# H1AR30.net
KiCad netlist of a schematic drawn in EAGLE
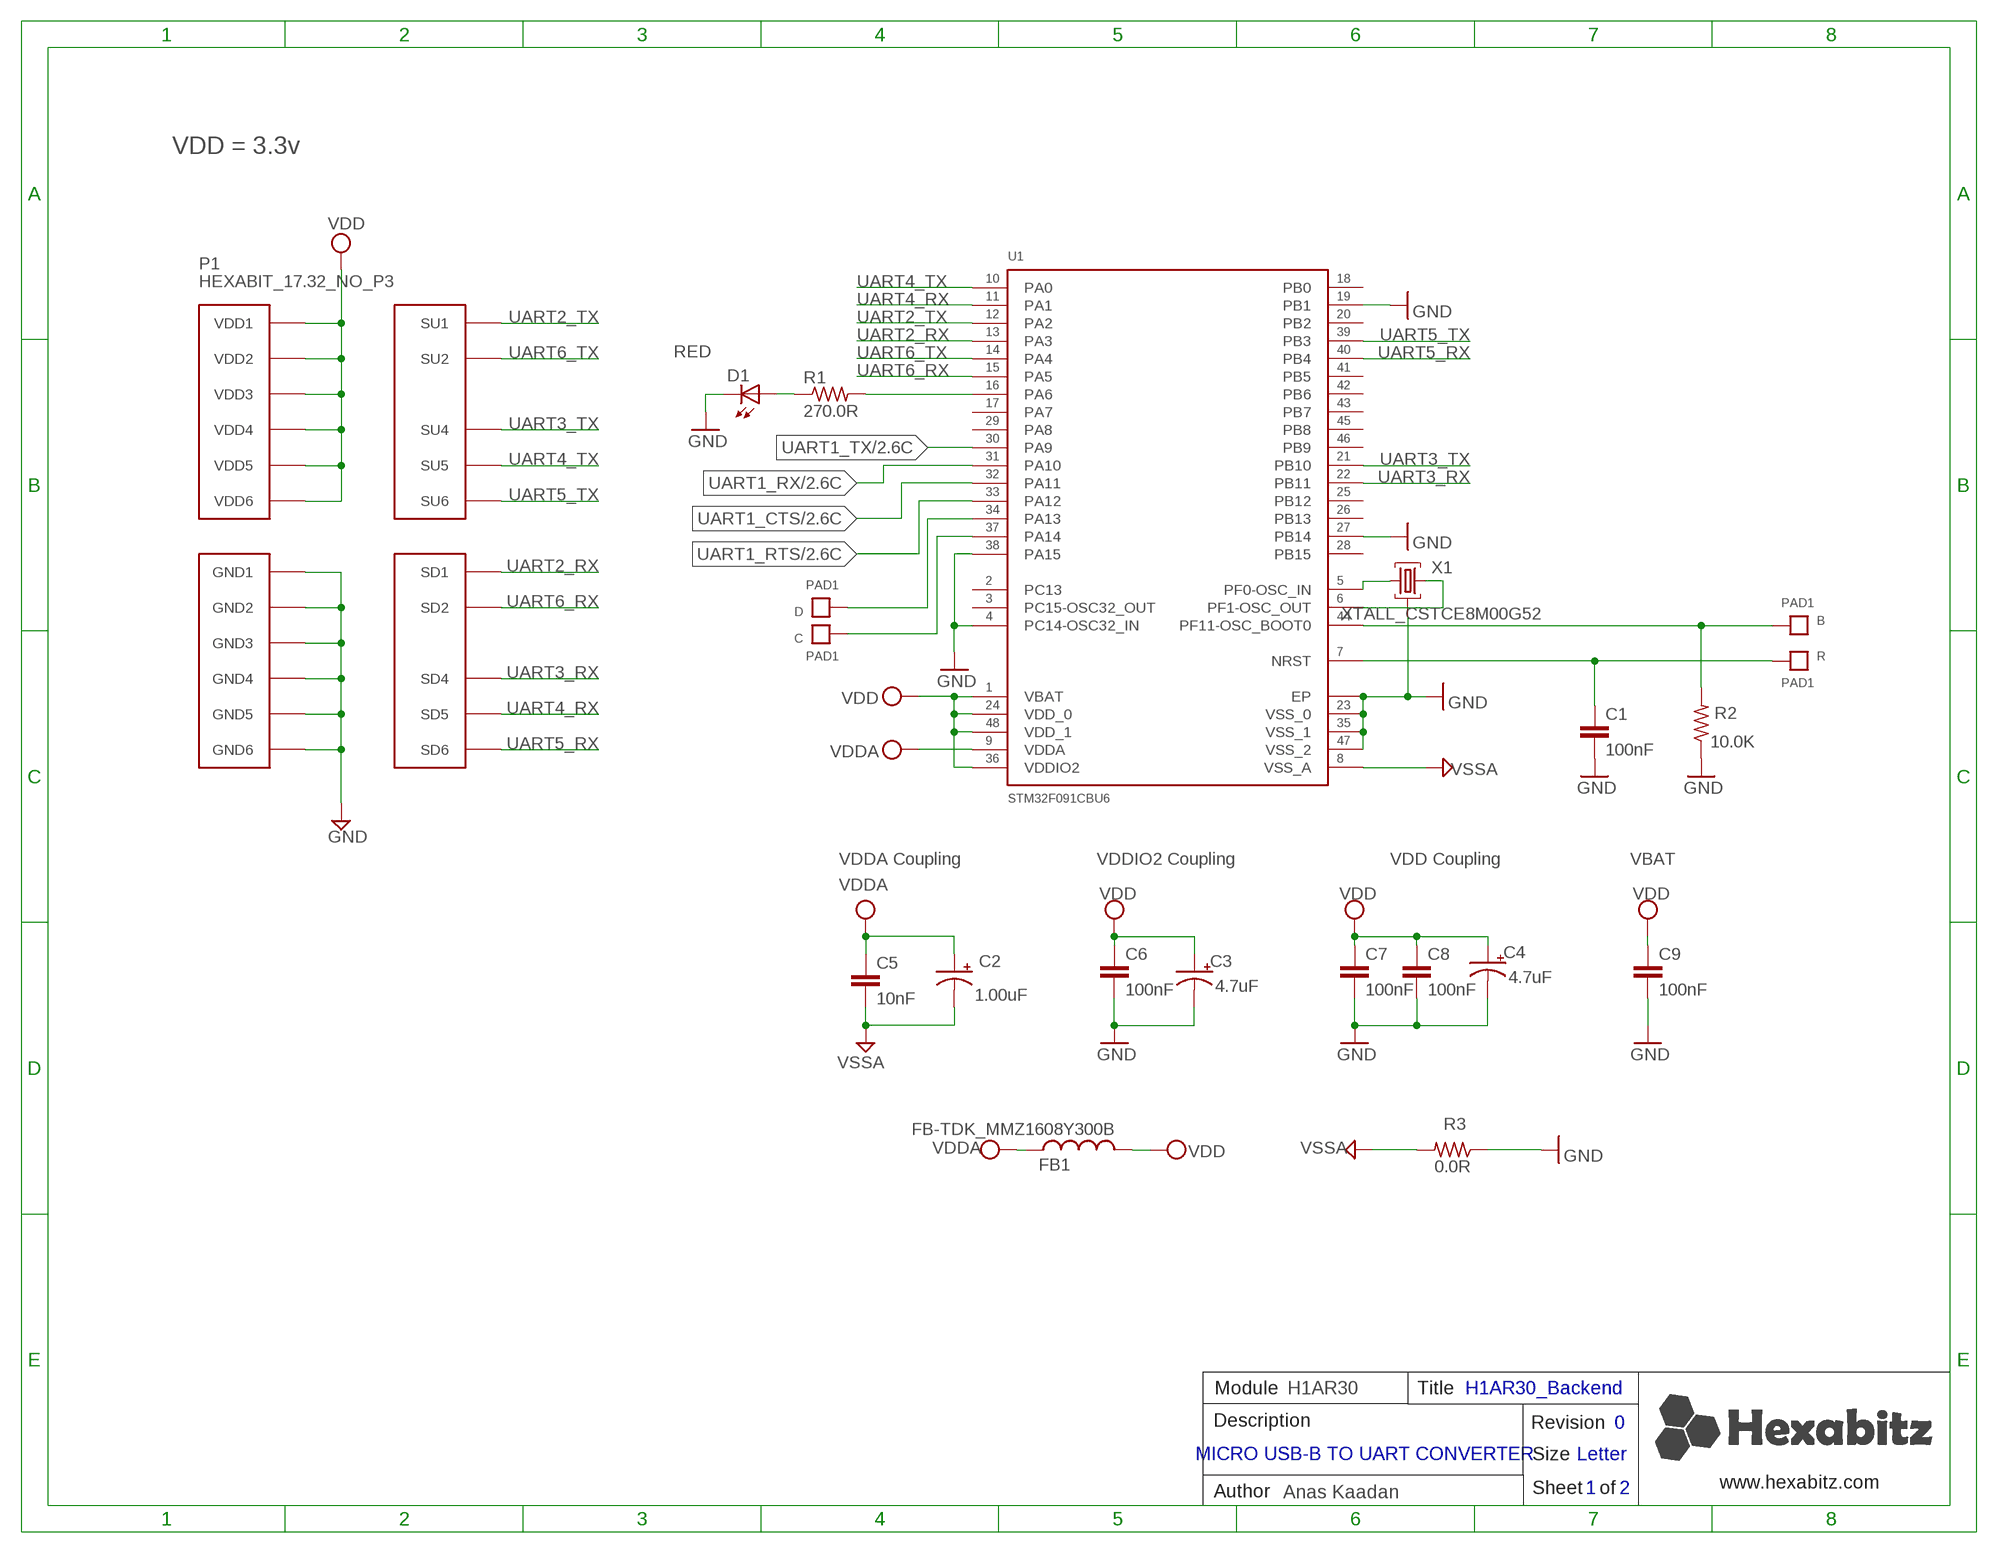
[diagram p0: schematic, sheet 1]
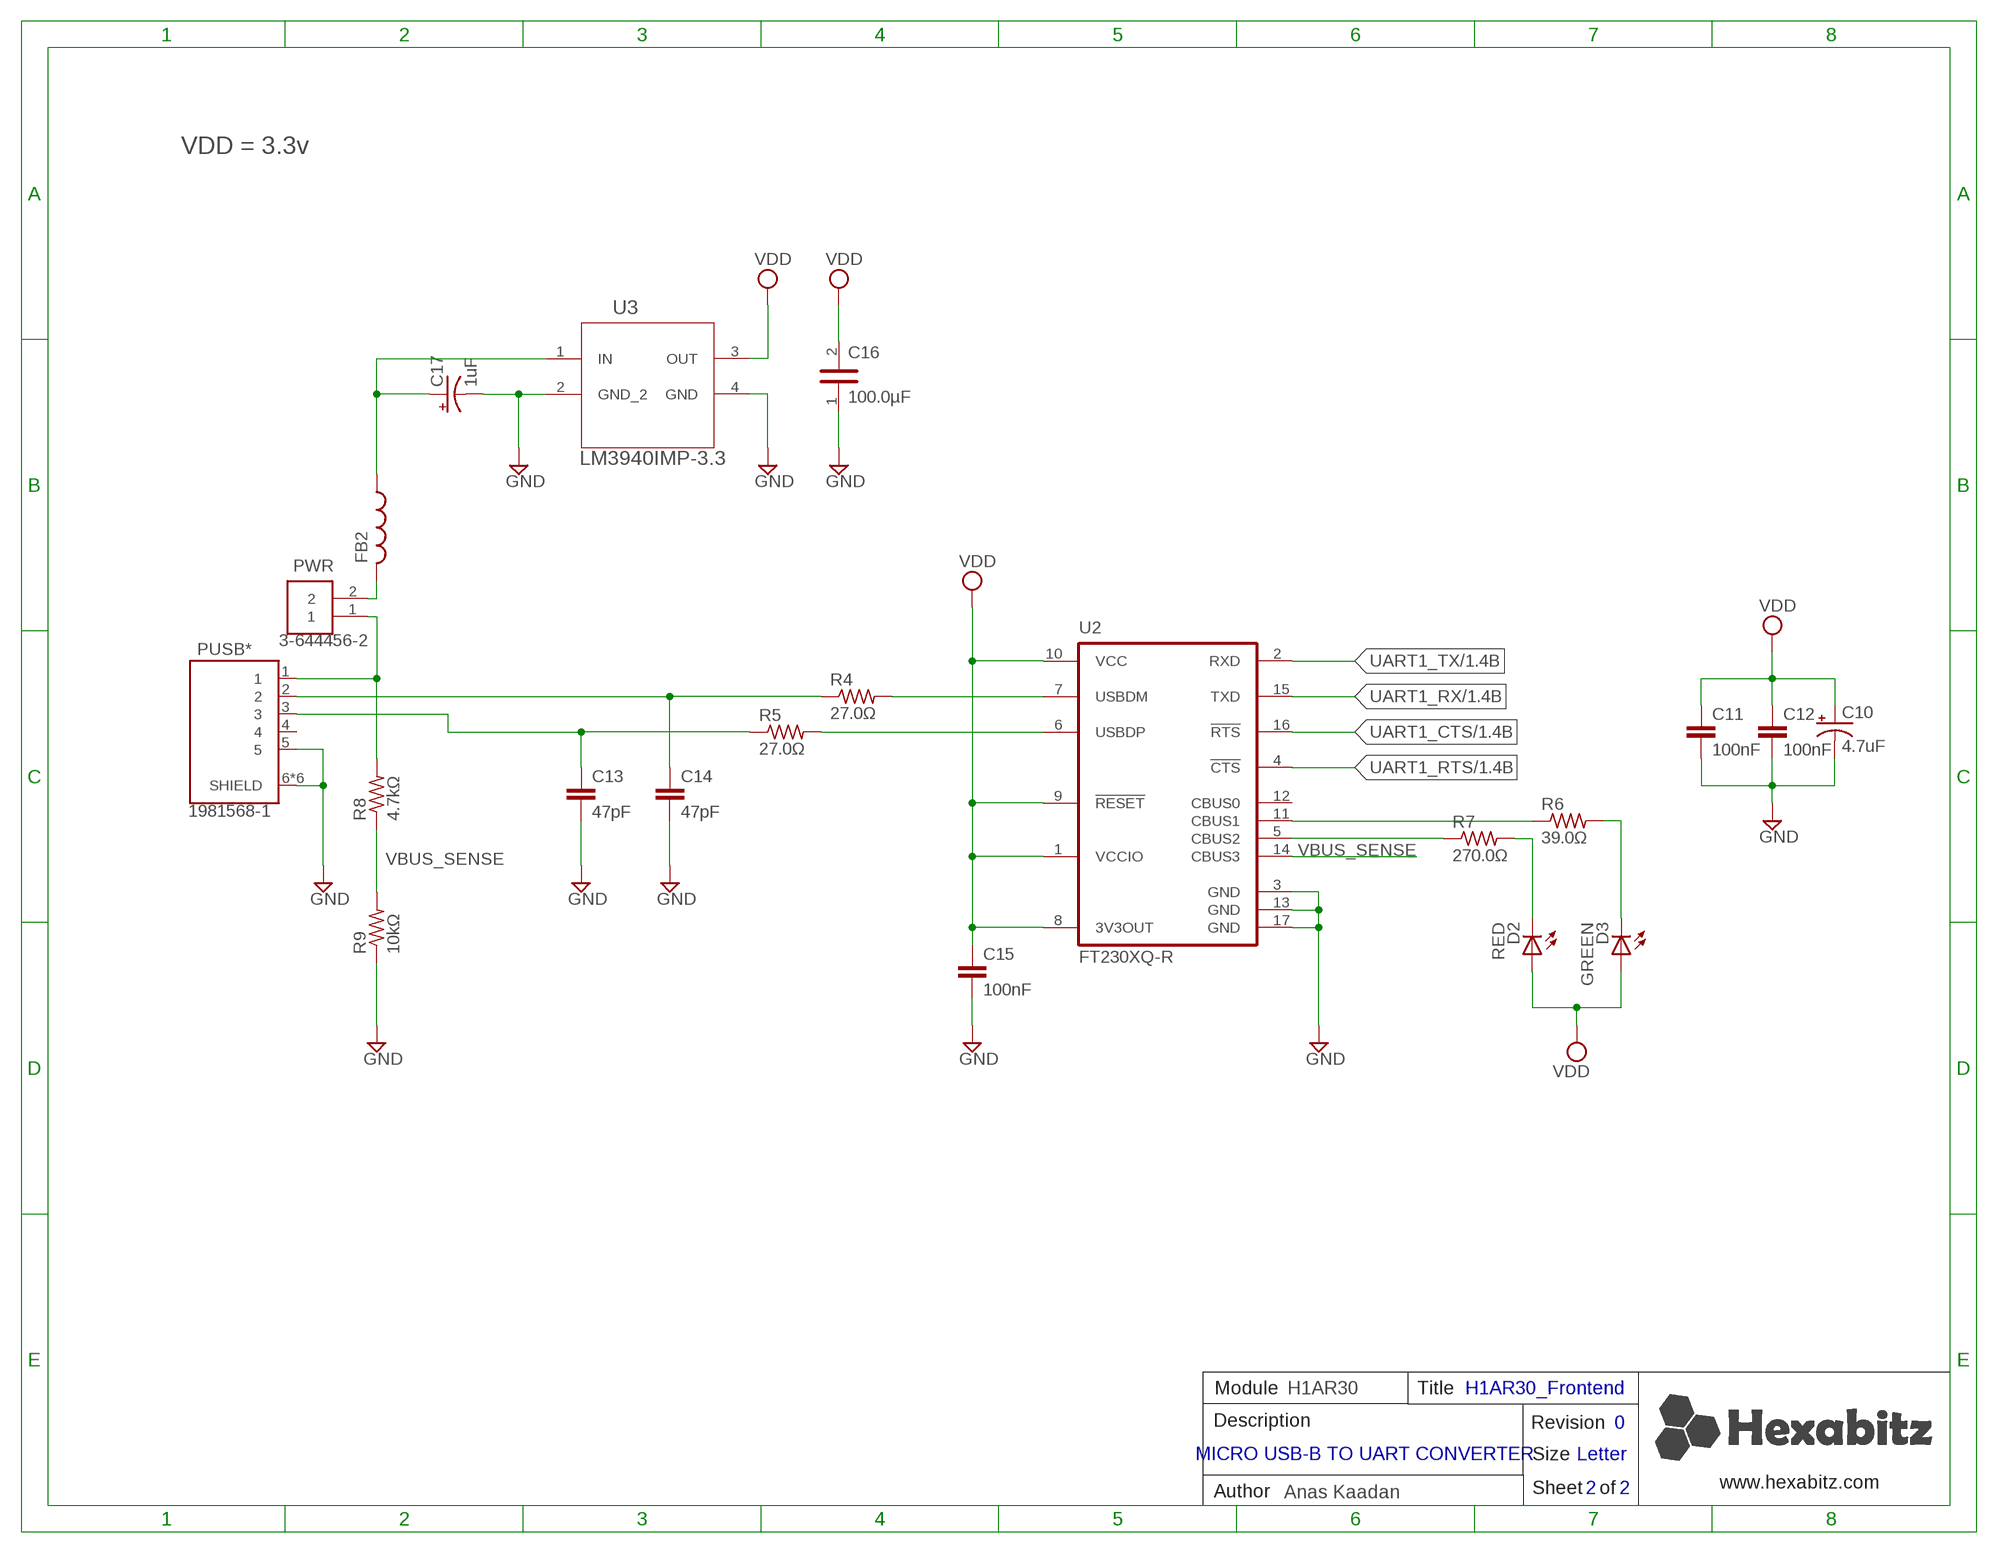
[diagram p1: schematic, sheet 2]

(export (version "E")
  (design (tool "Eeschema 10.0.6"))
  (components
    (comp (ref "C10")
      (value "4.7uF")
      (footprint "eagle-import:C-0805-POL")
      (fields
        (field (name "CAPACITANCE") "4.7 µF")
        (field (name "MFN") "Panasonic")
        (field (name "MPN") "10TPU4R7MSI")
        (field (name "OCTOPART_URL") "https://octopart.com/10tpu4r7msi-panasonic-29487748")
        (field (name "TOLERANCE") "±20%")
        (field (name "VOLTAGE_RATING") "10.0 V")
      )
      (libsource (lib "eagle-import") (part "C-0805-POL"))
    )
    (comp (ref "C11")
      (value "100nF")
      (footprint "eagle-import:C-0603")
      (fields
        (field (name "CAPACITANCE") "100 nF")
        (field (name "MFN") "AVX")
        (field (name "MPN") "0603YC104K4T2A")
        (field (name "OCTOPART_URL") "https://octopart.com/0603yc104k4t2a-avx+interconnect+%2F+elco-8120651")
        (field (name "TOLERANCE") "±10%")
        (field (name "VOLTAGE_RATING") "16.0 V")
      )
      (libsource (lib "eagle-import") (part "C-0603"))
    )
    (comp (ref "C12")
      (value "100nF")
      (footprint "eagle-import:C-0603")
      (fields
        (field (name "CAPACITANCE") "100 nF")
        (field (name "MFN") "AVX")
        (field (name "MPN") "0603YC104K4T2A")
        (field (name "OCTOPART_URL") "https://octopart.com/0603yc104k4t2a-avx+interconnect+%2F+elco-8120651")
        (field (name "TOLERANCE") "±10%")
        (field (name "VOLTAGE_RATING") "16.0 V")
      )
      (libsource (lib "eagle-import") (part "C-0603"))
    )
    (comp (ref "C13")
      (value "47pF")
      (footprint "eagle-import:C-0603")
      (fields
        (field (name "CAPACITANCE") "47 pF")
        (field (name "MFN") "AVX")
        (field (name "MPN") "06035A470JAT2A")
        (field (name "OCTOPART_URL") "https://octopart.com/c3225x5r0j107m250ac-tdk-25947844?r=spc#")
        (field (name "TOLERANCE") "±5%")
        (field (name "VOLTAGE_RATING") "50.0 V")
      )
      (libsource (lib "eagle-import") (part "C-0603"))
    )
    (comp (ref "C14")
      (value "47pF")
      (footprint "eagle-import:C-0603")
      (fields
        (field (name "CAPACITANCE") "47 pF")
        (field (name "MFN") "AVX")
        (field (name "MPN") "06035A470JAT2A")
        (field (name "OCTOPART_URL") "https://octopart.com/06035a470jat2a-avx+interconnect+%2F+elco-46507018")
        (field (name "TOLERANCE") "±5%")
        (field (name "VOLTAGE_RATING") "50.0 V")
      )
      (libsource (lib "eagle-import") (part "C-0603"))
    )
    (comp (ref "C15")
      (value "100nF")
      (footprint "eagle-import:C-0603")
      (fields
        (field (name "CAPACITANCE") "100 nF")
        (field (name "MFN") "AVX")
        (field (name "MPN") "0603YC104K4T2A")
        (field (name "OCTOPART_URL") "https://octopart.com/0603yc104k4t2a-avx+interconnect+%2F+elco-8120651")
        (field (name "TOLERANCE") "±10%")
        (field (name "VOLTAGE_RATING") "16.0 V")
      )
      (libsource (lib "eagle-import") (part "C-0603"))
    )
    (comp (ref "C16")
      (value "100uF")
      (footprint "eagle-import:C-3225")
      (fields
        (field (name "CAPACITANCE") "100.0µF")
        (field (name "MPN") "C3225X5R0J107M250AC")
        (field (name "VOLTAGE") "6.3V")
      )
      (libsource (lib "eagle-import") (part "C-3225TDK_C3225X5R0J107M250AC_0_0"))
    )
    (comp (ref "C17")
      (value "1uF")
      (footprint "eagle-import:C-0805-POL")
      (fields
        (field (name "CAPACITANCE") "1.00 µF")
        (field (name "MFN") "AVX")
        (field (name "MPN") "TAJR105M016RNJ")
        (field (name "OCTOPART_URL") "http://octopart.com/tajr105m016rnj-avx-1188552")
        (field (name "TOLERANCE") "±20%")
        (field (name "VOLTAGE_RATING") "16.0 V")
      )
      (libsource (lib "eagle-import") (part "C-0805-POL"))
    )
    (comp (ref "D2")
      (value "RED")
      (footprint "eagle-import:VLMS1300-GS08")
      (fields (field (name "MPN") "VLMS1300-GS08"))
      (libsource (lib "eagle-import") (part "VLMS1300-GS08"))
    )
    (comp (ref "D3")
      (value "GREEN")
      (footprint "eagle-import:VLMS1300-GS08")
      (fields (field (name "MPN") "VLMTG1300-GS08"))
      (libsource (lib "eagle-import") (part "VLMTG1300-GS08"))
    )
    (comp (ref "FB2")
      (value "FB-TDK_MMZ1608Y300B")
      (footprint "eagle-import:FB-TDK_MMZ1608Y300B")
      (fields
        (field (name "MFN") "TDK")
        (field (name "MPN") "MMZ1608Y300B")
        (field (name "OCTOPART_URL") "https://octopart.com/mmz1608y300b-tdk-368280")
      )
      (libsource (lib "eagle-import") (part "FB-TDK_MMZ1608Y300B"))
    )
    (comp (ref "PUSB*")
      (value "1981568-1")
      (footprint "eagle-import:TE_1981568-1")
      (fields (field (name "MPN") "19815681"))
      (libsource (lib "eagle-import") (part "1981568-1"))
    )
    (comp (ref "PWR")
      (value "3-644456-2")
      (footprint "eagle-import:TE_3-644456-2")
      (fields (field (name "MF") "TE Connectivity"))
      (libsource (lib "eagle-import") (part "3-644456-2"))
    )
    (comp (ref "R4")
      (value "27.0Ω")
      (footprint "eagle-import:R-0603")
      (fields
        (field (name "MFN") "Vishay")
        (field (name "MPN") "CRCW060327R0FKEA")
        (field (name "OCTOPART_URL") "https://octopart.com/crcw060327r0fkea-vishay-39833156")
        (field (name "RESISTANCE") "27.0 Ω")
        (field (name "TOLERANCE") "±1%")
      )
      (libsource (lib "eagle-import") (part "R-0603"))
    )
    (comp (ref "R5")
      (value "27.0Ω")
      (footprint "eagle-import:R-0603")
      (fields
        (field (name "MFN") "Vishay")
        (field (name "MPN") "CRCW060327R0FKEA")
        (field (name "OCTOPART_URL") "https://octopart.com/crcw060327r0fkea-vishay-39833156")
        (field (name "RESISTANCE") "27.0 Ω")
        (field (name "TOLERANCE") "±1%")
      )
      (libsource (lib "eagle-import") (part "R-0603"))
    )
    (comp (ref "R6")
      (value "39.0Ω")
      (footprint "eagle-import:R-0603")
      (fields
        (field (name "MFN") "Panasonic")
        (field (name "MPN") "ERJ-3GEYJ390V")
        (field (name "OCTOPART_URL") "https://octopart.com/erj-3geyj390v-panasonic-55422095")
        (field (name "RESISTANCE") "39.0 Ω")
        (field (name "TOLERANCE") "±5%")
      )
      (libsource (lib "eagle-import") (part "R-0603"))
    )
    (comp (ref "R7")
      (value "270.0Ω")
      (footprint "eagle-import:R-0603")
      (fields
        (field (name "MFN") "Panasonic")
        (field (name "MPN") "ERJ-3GEYJ271V")
        (field (name "OCTOPART_URL") "https://octopart.com/erj-3geyj271v-panasonic-55560546")
        (field (name "RESISTANCE") "270.0 Ω")
        (field (name "TOLERANCE") "±5%")
      )
      (libsource (lib "eagle-import") (part "R-0603"))
    )
    (comp (ref "R8")
      (value "4.7kΩ")
      (footprint "eagle-import:R-0603")
      (fields
        (field (name "MFN") "Vishay")
        (field (name "MPN") "CRCW06034K70FKEA")
        (field (name "OCTOPART_URL") "http://octopart.com/crcw06034k70fkea-vishay-39455708")
        (field (name "RESISTANCE") "4.7 kΩ")
        (field (name "TOLERANCE") "±1%")
      )
      (libsource (lib "eagle-import") (part "R-0603"))
    )
    (comp (ref "R9")
      (value "10kΩ")
      (footprint "eagle-import:R-0603")
      (fields
        (field (name "MFN") "Vishay")
        (field (name "MPN") "CRCW060310K0JNEB")
        (field (name "OCTOPART_URL") "https://octopart.com/crcw060310k0jneb-vishay+dale-46603268")
        (field (name "RESISTANCE") "10.0 kΩ")
        (field (name "TOLERANCE") "±5%")
      )
      (libsource (lib "eagle-import") (part "R-0603"))
    )
    (comp (ref "U2")
      (value "FT230XQ-R")
      (footprint "eagle-import:QFN16")
      (libsource (lib "eagle-import") (part "FT230XQ-R"))
    )
    (comp (ref "U3")
      (value "LM3940IMP-3.3")
      (footprint "eagle-import:SOT230P696X180-4N")
      (fields (field (name "MPN") "LM3940IMP-3.3/NOPB"))
      (libsource (lib "eagle-import") (part "LM3940IMP-3.3"))
    )
    (comp (ref "B")
      (value "PAD1")
      (footprint "eagle-import:PAD1")
      (libsource (lib "eagle-import") (part "PAD1"))
    )
    (comp (ref "C")
      (value "PAD1")
      (footprint "eagle-import:PAD1")
      (libsource (lib "eagle-import") (part "PAD1"))
    )
    (comp (ref "C1")
      (value "100nF")
      (footprint "eagle-import:C-0603")
      (fields
        (field (name "CAPACITANCE") "100nF")
        (field (name "MFN") "KEMET")
        (field (name "MPN") "C0603C104K8RACTU")
        (field (name "OCTOPART_URL") "https://octopart.com/c0603c104k8ractu-kemet-145075?r=sp&s=9bS9ASSwSEqMCE9KBEQZ0g")
        (field (name "TOLERANCE") "10%")
        (field (name "VOLTAGE_RATING") "10V")
      )
      (libsource (lib "eagle-import") (part "C-0603"))
    )
    (comp (ref "C2")
      (value "1.00uF")
      (footprint "eagle-import:C-0805-POL")
      (fields
        (field (name "CAPACITANCE") "1.00uF")
        (field (name "MFN") "Yageo")
        (field (name "MPN") "CC0805KKX7R7BB105")
        (field (name "OCTOPART_URL") "https://octopart.com/cc0805kkx7r7bb105-yageo-8376555?r=sp&s=YKl1wwtkROau_X5nniH2ig")
        (field (name "TOLERANCE") "10%")
        (field (name "VOLTAGE_RATING") "16V")
      )
      (libsource (lib "eagle-import") (part "C-0805-POL"))
    )
    (comp (ref "C3")
      (value "4.7uF")
      (footprint "eagle-import:C-0805-POL")
      (fields
        (field (name "CAPACITANCE") "4.7uF")
        (field (name "MFN") "Murata")
        (field (name "MPN") "GRM21BC81E475KA12L")
        (field (name "OCTOPART_URL") "https://octopart.com/grm21bc81e475ka12l-murata-10331911?r=sp&s=RY3qZSD8T6mG6TC9CHI5qQ")
        (field (name "TOLERANCE") "10%")
        (field (name "VOLTAGE_RATING") "25V")
      )
      (libsource (lib "eagle-import") (part "C-0805-POL"))
    )
    (comp (ref "C4")
      (value "4.7uF")
      (footprint "eagle-import:C-0805-POL")
      (fields
        (field (name "CAPACITANCE") "4.7uF")
        (field (name "MFN") "Murata")
        (field (name "MPN") "GRM21BC81E475KA12L")
        (field (name "OCTOPART_URL") "https://octopart.com/grm21bc81e475ka12l-murata-10331911?r=sp&s=RY3qZSD8T6mG6TC9CHI5qQ")
        (field (name "TOLERANCE") "10%")
        (field (name "VOLTAGE_RATING") "25V")
      )
      (libsource (lib "eagle-import") (part "C-0805-POL"))
    )
    (comp (ref "C5")
      (value "10nF")
      (footprint "eagle-import:C-0603")
      (fields
        (field (name "CAPACITANCE") "10nF")
        (field (name "MFN") "KEMET")
        (field (name "MPN") "C0603C103K5RACTU")
        (field (name "OCTOPART_URL") "https://octopart.com/c0603c103k5ractu-kemet-133094?r=sp&s=R_iPBxLnSmGqhkU2rIMFpg")
        (field (name "TOLERANCE") "10%")
        (field (name "VOLTAGE_RATING") "50V")
      )
      (libsource (lib "eagle-import") (part "C-0603"))
    )
    (comp (ref "C6")
      (value "100nF")
      (footprint "eagle-import:C-0603")
      (fields
        (field (name "CAPACITANCE") "100nF")
        (field (name "MFN") "KEMET")
        (field (name "MPN") "C0603C104K8RACTU")
        (field (name "OCTOPART_URL") "https://octopart.com/c0603c104k8ractu-kemet-145075?r=sp&s=9bS9ASSwSEqMCE9KBEQZ0g")
        (field (name "TOLERANCE") "10%")
        (field (name "VOLTAGE_RATING") "10V")
      )
      (libsource (lib "eagle-import") (part "C-0603"))
    )
    (comp (ref "C7")
      (value "100nF")
      (footprint "eagle-import:C-0603")
      (fields
        (field (name "CAPACITANCE") "100nF")
        (field (name "MFN") "KEMET")
        (field (name "MPN") "C0603C104K8RACTU")
        (field (name "OCTOPART_URL") "https://octopart.com/c0603c104k8ractu-kemet-145075?r=sp&s=9bS9ASSwSEqMCE9KBEQZ0g")
        (field (name "TOLERANCE") "10%")
        (field (name "VOLTAGE_RATING") "10")
      )
      (libsource (lib "eagle-import") (part "C-0603"))
    )
    (comp (ref "C8")
      (value "100nF")
      (footprint "eagle-import:C-0603")
      (fields
        (field (name "CAPACITANCE") "100nF")
        (field (name "MFN") "KEMET")
        (field (name "MPN") "C0603C104K8RACTU")
        (field (name "OCTOPART_URL") "https://octopart.com/c0603c104k8ractu-kemet-145075?r=sp&s=9bS9ASSwSEqMCE9KBEQZ0g")
        (field (name "TOLERANCE") "10%")
        (field (name "VOLTAGE_RATING") "10V")
      )
      (libsource (lib "eagle-import") (part "C-0603"))
    )
    (comp (ref "C9")
      (value "100nF")
      (footprint "eagle-import:C-0603")
      (fields
        (field (name "CAPACITANCE") "100nF")
        (field (name "MFN") "KEMET")
        (field (name "MPN") "C0603C104K8RACTU")
        (field (name "OCTOPART_URL") "https://octopart.com/c0603c104k8ractu-kemet-145075?r=sp&s=9bS9ASSwSEqMCE9KBEQZ0g")
        (field (name "TOLERANCE") "10V")
        (field (name "VOLTAGE_RATING") "10%")
      )
      (libsource (lib "eagle-import") (part "C-0603"))
    )
    (comp (ref "D")
      (value "PAD1")
      (footprint "eagle-import:PAD1")
      (libsource (lib "eagle-import") (part "PAD1"))
    )
    (comp (ref "D1")
      (value "RED")
      (footprint "eagle-import:VLMS1300-GS08")
      (fields
        (field (name "MPN") "VLMS1300-GS08")
        (field (name "MFN") "Vishay")
        (field (name "MPN_1") "VLMS1300-GS08")
        (field (name "OCTOPART_URL") "https://octopart.com/vlms1300-gs08-vishay-21709201?r=sp&s=_gcP4_q8T1SC6PJQPTQ9yA")
      )
      (libsource (lib "eagle-import") (part "VLMS1300-GS08"))
    )
    (comp (ref "FB1")
      (value "FB-TDK_MMZ1608Y300B")
      (footprint "eagle-import:FB-TDK_MMZ1608Y300B")
      (fields
        (field (name "MFN") "TDK ")
        (field (name "MPN") "MMZ1608Y300B")
        (field (name "OCTOPART_URL") "https://octopart.com/mmz1608y300b-tdk-368280?r=sp&s=cd9_2ZEqQ9q9UNBuQgHAiA")
      )
      (libsource (lib "eagle-import") (part "FB-TDK_MMZ1608Y300B"))
    )
    (comp (ref "P1")
      (value "HEXABIT_17.32_NO_P3")
      (footprint "eagle-import:HEXABIT_17.32_NO_P3")
      (libsource (lib "eagle-import") (part "HEXABIT_?_NO_P317.32"))
    )
    (comp (ref "R")
      (value "PAD1")
      (footprint "eagle-import:PAD1")
      (libsource (lib "eagle-import") (part "PAD1"))
    )
    (comp (ref "R1")
      (value "270.0R")
      (footprint "eagle-import:R-0603")
      (fields
        (field (name "MFN") "Yageo")
        (field (name "MPN") "RC0603FR-07270RL")
        (field (name "OCTOPART_URL") "https://octopart.com/search?q=RC0603FR-07270RL&start=0")
        (field (name "RESISTANCE") "270.0 Ohm")
        (field (name "TOLERANCE") "1%")
      )
      (libsource (lib "eagle-import") (part "R-0603"))
    )
    (comp (ref "R2")
      (value "10.0K")
      (footprint "eagle-import:R-0603")
      (fields
        (field (name "MFN") "Vishay")
        (field (name "MPN") "CRCW060310K0JNEB")
        (field (name "OCTOPART_URL") "https://octopart.com/crcw060310k0jneb-vishay+dale-46603268")
        (field (name "RESISTANCE") "10.0K Ohm")
        (field (name "TOLERANCE") "5%")
      )
      (libsource (lib "eagle-import") (part "R-0603"))
    )
    (comp (ref "R3")
      (value "0.0R")
      (footprint "eagle-import:R-0603")
      (fields
        (field (name "MFN") "Yageo")
        (field (name "MPN") "RC0603JR-070RL")
        (field (name "OCTOPART_URL") "https://octopart.com/rc0603jr-070rl-yageo-1241539?r=sp&s=X2NteqRjRNWrnx42Y0aliA")
        (field (name "RESISTANCE") "0.0 Ohm")
      )
      (libsource (lib "eagle-import") (part "R-0603"))
    )
    (comp (ref "U1")
      (value "STM32F091CBU6")
      (footprint "eagle-import:STM32F091CBU6")
      (libsource (lib "eagle-import") (part "STM32F091CBU6"))
    )
    (comp (ref "X1")
      (value "XTALL_CSTCE8M00G52")
      (footprint "eagle-import:XTALL_CSTCE8M00G52")
      (fields (field (name "MPN") "CSTCE8M00G52Z-R0"))
      (libsource (lib "eagle-import") (part "XTALL_CSTCE8M00G52"))
    )
  )
  (nets
    (net (code "1") (name "GND") (class "Default")
      (node (ref "C1") (pin "2") (pinfunction "2_2") (pintype "passive"))
      (node (ref "C10") (pin "2") (pinfunction "-_2") (pintype "passive"))
      (node (ref "C11") (pin "2") (pinfunction "2_2") (pintype "passive"))
      (node (ref "C12") (pin "2") (pinfunction "2_2") (pintype "passive"))
      (node (ref "C13") (pin "2") (pinfunction "2_2") (pintype "passive"))
      (node (ref "C14") (pin "2") (pinfunction "2_2") (pintype "passive"))
      (node (ref "C15") (pin "2") (pinfunction "2_2") (pintype "passive"))
      (node (ref "C16") (pin "1") (pinfunction "1_1") (pintype "bidirectional"))
      (node (ref "C17") (pin "2") (pinfunction "-_2") (pintype "passive"))
      (node (ref "C3") (pin "2") (pinfunction "-_2") (pintype "passive"))
      (node (ref "C4") (pin "2") (pinfunction "-_2") (pintype "passive"))
      (node (ref "C6") (pin "2") (pinfunction "2_2") (pintype "passive"))
      (node (ref "C7") (pin "2") (pinfunction "2_2") (pintype "passive"))
      (node (ref "C8") (pin "2") (pinfunction "2_2") (pintype "passive"))
      (node (ref "C9") (pin "2") (pinfunction "2_2") (pintype "passive"))
      (node (ref "D1") (pin "C") (pinfunction "C_C") (pintype "passive"))
      (node (ref "P1") (pin "PAD_PD10") (pinfunction "GND4_PAD_PD10") (pintype "power_in"))
      (node (ref "P1") (pin "PAD_PD11") (pinfunction "GND5_PAD_PD11") (pintype "power_in"))
      (node (ref "P1") (pin "PAD_PD12") (pinfunction "GND6_PAD_PD12") (pintype "power_in"))
      (node (ref "P1") (pin "PAD_PD7") (pinfunction "GND1_PAD_PD7") (pintype "power_in"))
      (node (ref "P1") (pin "PAD_PD8") (pinfunction "GND2_PAD_PD8") (pintype "power_in"))
      (node (ref "P1") (pin "PAD_PD9") (pinfunction "GND3_PAD_PD9") (pintype "power_in"))
      (node (ref "PUSB*") (pin "10") (pinfunction "SHIELD_10") (pintype "passive"))
      (node (ref "PUSB*") (pin "11") (pinfunction "SHIELD_11") (pintype "passive"))
      (node (ref "PUSB*") (pin "5") (pinfunction "5_5") (pintype "passive"))
      (node (ref "PUSB*") (pin "6") (pinfunction "SHIELD_6") (pintype "passive"))
      (node (ref "PUSB*") (pin "7") (pinfunction "SHIELD_7") (pintype "passive"))
      (node (ref "PUSB*") (pin "8") (pinfunction "SHIELD_8") (pintype "passive"))
      (node (ref "PUSB*") (pin "9") (pinfunction "SHIELD_9") (pintype "passive"))
      (node (ref "R2") (pin "1") (pinfunction "1_1") (pintype "passive"))
      (node (ref "R3") (pin "1") (pinfunction "1_1") (pintype "passive"))
      (node (ref "R9") (pin "1") (pinfunction "1_1") (pintype "passive"))
      (node (ref "U1") (pin "EP") (pinfunction "EP_EP") (pintype "power_in"))
      (node (ref "U1") (pin "P$19") (pinfunction "PB1_P$19") (pintype "bidirectional"))
      (node (ref "U1") (pin "P$23") (pinfunction "VSS_0_P$23") (pintype "power_in"))
      (node (ref "U1") (pin "P$27") (pinfunction "PB14_P$27") (pintype "bidirectional"))
      (node (ref "U1") (pin "P$3") (pinfunction "PC14-OSC32_IN_P$3") (pintype "bidirectional"))
      (node (ref "U1") (pin "P$35") (pinfunction "VSS_1_P$35") (pintype "power_in"))
      (node (ref "U1") (pin "P$38") (pinfunction "PA15_P$38") (pintype "bidirectional"))
      (node (ref "U1") (pin "P$47") (pinfunction "VSS_2_P$47") (pintype "power_in"))
      (node (ref "U2") (pin "13") (pinfunction "GND_13") (pintype "power_in"))
      (node (ref "U2") (pin "17") (pinfunction "GND_17") (pintype "power_in"))
      (node (ref "U2") (pin "3") (pinfunction "GND_3") (pintype "power_in"))
      (node (ref "U3") (pin "2") (pinfunction "GND_2_2") (pintype "passive"))
      (node (ref "U3") (pin "4") (pinfunction "GND_4") (pintype "passive"))
      (node (ref "X1") (pin "P$2") (pinfunction "2_P$2") (pintype "passive"))
    )
    (net (code "2") (name "Net-(C13-Pad1)") (class "Default")
      (node (ref "C13") (pin "1") (pinfunction "1_1") (pintype "passive"))
      (node (ref "PUSB*") (pin "3") (pinfunction "3_3") (pintype "passive"))
      (node (ref "R5") (pin "1") (pinfunction "1_1") (pintype "passive"))
    )
    (net (code "3") (name "Net-(C14-Pad1)") (class "Default")
      (node (ref "C14") (pin "1") (pinfunction "1_1") (pintype "passive"))
      (node (ref "PUSB*") (pin "2") (pinfunction "2_2") (pintype "passive"))
      (node (ref "R4") (pin "1") (pinfunction "1_1") (pintype "passive"))
    )
    (net (code "4") (name "Net-(C17-+)") (class "Default")
      (node (ref "C17") (pin "1") (pinfunction "+_1") (pintype "passive"))
      (node (ref "FB2") (pin "1") (pinfunction "1_1") (pintype "passive"))
      (node (ref "U3") (pin "1") (pinfunction "IN_1") (pintype "power_in"))
    )
    (net (code "5") (name "Net-(D1-PadA)") (class "Default")
      (node (ref "D1") (pin "A") (pinfunction "A_A") (pintype "passive"))
      (node (ref "R1") (pin "1") (pinfunction "1_1") (pintype "passive"))
    )
    (net (code "6") (name "Net-(D2-PadC)") (class "Default")
      (node (ref "D2") (pin "C") (pinfunction "C_C") (pintype "passive"))
      (node (ref "R7") (pin "2") (pinfunction "2_2") (pintype "passive"))
    )
    (net (code "7") (name "Net-(D3-PadC)") (class "Default")
      (node (ref "D3") (pin "C") (pinfunction "C_C") (pintype "passive"))
      (node (ref "R6") (pin "2") (pinfunction "2_2") (pintype "passive"))
    )
    (net (code "8") (name "Net-(FB2-Pad2)") (class "Default")
      (node (ref "FB2") (pin "2") (pinfunction "2_2") (pintype "passive"))
      (node (ref "PWR") (pin "2") (pinfunction "2_2") (pintype "passive"))
    )
    (net (code "9") (name "Net-(PUSB*-Pad1)") (class "Default")
      (node (ref "PUSB*") (pin "1") (pinfunction "1_1") (pintype "passive"))
      (node (ref "PWR") (pin "1") (pinfunction "1_1") (pintype "passive"))
      (node (ref "R8") (pin "2") (pinfunction "2_2") (pintype "passive"))
    )
    (net (code "10") (name "Net-(U1-NRST)") (class "Default")
      (node (ref "C1") (pin "1") (pinfunction "1_1") (pintype "passive"))
      (node (ref "R") (pin "P$1") (pinfunction "P$1_P$1") (pintype "passive"))
      (node (ref "R") (pin "P$2") (pinfunction "P$1_P$2") (pintype "passive"))
      (node (ref "U1") (pin "P$7") (pinfunction "NRST_P$7") (pintype "passive"))
    )
    (net (code "11") (name "Net-(U1-PA6)") (class "Default")
      (node (ref "R1") (pin "2") (pinfunction "2_2") (pintype "passive"))
      (node (ref "U1") (pin "P$16") (pinfunction "PA6_P$16") (pintype "bidirectional"))
    )
    (net (code "12") (name "Net-(U1-PA13)") (class "Default")
      (node (ref "D") (pin "P$1") (pinfunction "P$1_P$1") (pintype "passive"))
      (node (ref "D") (pin "P$2") (pinfunction "P$1_P$2") (pintype "passive"))
      (node (ref "U1") (pin "P$34") (pinfunction "PA13_P$34") (pintype "bidirectional"))
    )
    (net (code "13") (name "Net-(U1-PA14)") (class "Default")
      (node (ref "C") (pin "P$1") (pinfunction "P$1_P$1") (pintype "passive"))
      (node (ref "C") (pin "P$2") (pinfunction "P$1_P$2") (pintype "passive"))
      (node (ref "U1") (pin "P$37") (pinfunction "PA14_P$37") (pintype "bidirectional"))
    )
    (net (code "14") (name "Net-(U1-PF0-OSC_IN)") (class "Default")
      (node (ref "U1") (pin "P$5") (pinfunction "PF0-OSC_IN_P$5") (pintype "bidirectional"))
      (node (ref "X1") (pin "P$1") (pinfunction "1_P$1") (pintype "passive"))
    )
    (net (code "15") (name "Net-(U1-PF1-OSC_OUT)") (class "Default")
      (node (ref "U1") (pin "P$6") (pinfunction "PF1-OSC_OUT_P$6") (pintype "bidirectional"))
      (node (ref "X1") (pin "P$3") (pinfunction "3_P$3") (pintype "passive"))
    )
    (net (code "16") (name "Net-(U1-PF11-OSC_BOOT0)") (class "Default")
      (node (ref "B") (pin "P$1") (pinfunction "P$1_P$1") (pintype "passive"))
      (node (ref "B") (pin "P$2") (pinfunction "P$1_P$2") (pintype "passive"))
      (node (ref "R2") (pin "2") (pinfunction "2_2") (pintype "passive"))
      (node (ref "U1") (pin "P$44") (pinfunction "PF11-OSC_BOOT0_P$44") (pintype "bidirectional"))
    )
    (net (code "17") (name "Net-(U2-CBUS1)") (class "Default")
      (node (ref "R6") (pin "1") (pinfunction "1_1") (pintype "passive"))
      (node (ref "U2") (pin "11") (pinfunction "CBUS1_11") (pintype "bidirectional"))
    )
    (net (code "18") (name "Net-(U2-CBUS2)") (class "Default")
      (node (ref "R7") (pin "1") (pinfunction "1_1") (pintype "passive"))
      (node (ref "U2") (pin "5") (pinfunction "CBUS2_5") (pintype "bidirectional"))
    )
    (net (code "19") (name "Net-(U2-USBDM)") (class "Default")
      (node (ref "R4") (pin "2") (pinfunction "2_2") (pintype "passive"))
      (node (ref "U2") (pin "7") (pinfunction "USBDM_7") (pintype "bidirectional"))
    )
    (net (code "20") (name "Net-(U2-USBDP)") (class "Default")
      (node (ref "R5") (pin "2") (pinfunction "2_2") (pintype "passive"))
      (node (ref "U2") (pin "6") (pinfunction "USBDP_6") (pintype "bidirectional"))
    )
    (net (code "21") (name "UART1_CTS") (class "Default")
      (node (ref "U1") (pin "P$32") (pinfunction "PA11_P$32") (pintype "bidirectional"))
      (node (ref "U2") (pin "16") (pinfunction "~{RTS}_16") (pintype "output"))
    )
    (net (code "22") (name "UART1_RTS") (class "Default")
      (node (ref "U1") (pin "P$33") (pinfunction "PA12_P$33") (pintype "bidirectional"))
      (node (ref "U2") (pin "4") (pinfunction "~{CTS}_4") (pintype "input"))
    )
    (net (code "23") (name "UART1_RX") (class "Default")
      (node (ref "U1") (pin "P$31") (pinfunction "PA10_P$31") (pintype "bidirectional"))
      (node (ref "U2") (pin "15") (pinfunction "TXD_15") (pintype "output"))
    )
    (net (code "24") (name "UART1_TX") (class "Default")
      (node (ref "U1") (pin "P$30") (pinfunction "PA9_P$30") (pintype "bidirectional"))
      (node (ref "U2") (pin "2") (pinfunction "RXD_2") (pintype "input"))
    )
    (net (code "25") (name "UART2_RX") (class "Default")
      (node (ref "P1") (pin "PAD_PD1") (pinfunction "SD1_PAD_PD1") (pintype "bidirectional"))
      (node (ref "U1") (pin "P$13") (pinfunction "PA3_P$13") (pintype "bidirectional"))
    )
    (net (code "26") (name "UART2_TX") (class "Default")
      (node (ref "P1") (pin "PAD_PU1") (pinfunction "SU1_PAD_PU1") (pintype "bidirectional"))
      (node (ref "U1") (pin "P$12") (pinfunction "PA2_P$12") (pintype "bidirectional"))
    )
    (net (code "27") (name "UART3_RX") (class "Default")
      (node (ref "P1") (pin "PAD_PD4") (pinfunction "SD4_PAD_PD4") (pintype "bidirectional"))
      (node (ref "U1") (pin "P$22") (pinfunction "PB11_P$22") (pintype "bidirectional"))
    )
    (net (code "28") (name "UART3_TX") (class "Default")
      (node (ref "P1") (pin "PAD_PU4") (pinfunction "SU4_PAD_PU4") (pintype "bidirectional"))
      (node (ref "U1") (pin "P$21") (pinfunction "PB10_P$21") (pintype "bidirectional"))
    )
    (net (code "29") (name "UART4_RX") (class "Default")
      (node (ref "P1") (pin "PAD_PD5") (pinfunction "SD5_PAD_PD5") (pintype "bidirectional"))
      (node (ref "U1") (pin "P$11") (pinfunction "PA1_P$11") (pintype "bidirectional"))
    )
    (net (code "30") (name "UART4_TX") (class "Default")
      (node (ref "P1") (pin "PAD_PU5") (pinfunction "SU5_PAD_PU5") (pintype "bidirectional"))
      (node (ref "U1") (pin "P$10") (pinfunction "PA0_P$10") (pintype "bidirectional"))
    )
    (net (code "31") (name "UART5_RX") (class "Default")
      (node (ref "P1") (pin "PAD_PD6") (pinfunction "SD6_PAD_PD6") (pintype "bidirectional"))
      (node (ref "U1") (pin "P$40") (pinfunction "PB4_P$40") (pintype "bidirectional"))
    )
    (net (code "32") (name "UART5_TX") (class "Default")
      (node (ref "P1") (pin "PAD_PU6") (pinfunction "SU6_PAD_PU6") (pintype "bidirectional"))
      (node (ref "U1") (pin "P$39") (pinfunction "PB3_P$39") (pintype "bidirectional"))
    )
    (net (code "33") (name "UART6_RX") (class "Default")
      (node (ref "P1") (pin "PAD_PD2") (pinfunction "SD2_PAD_PD2") (pintype "bidirectional"))
      (node (ref "U1") (pin "P$15") (pinfunction "PA5_P$15") (pintype "bidirectional"))
    )
    (net (code "34") (name "UART6_TX") (class "Default")
      (node (ref "P1") (pin "PAD_PU2") (pinfunction "SU2_PAD_PU2") (pintype "bidirectional"))
      (node (ref "U1") (pin "P$14") (pinfunction "PA4_P$14") (pintype "bidirectional"))
    )
    (net (code "35") (name "VBUS_SENSE") (class "Default")
      (node (ref "R8") (pin "1") (pinfunction "1_1") (pintype "passive"))
      (node (ref "R9") (pin "2") (pinfunction "2_2") (pintype "passive"))
      (node (ref "U2") (pin "14") (pinfunction "CBUS3_14") (pintype "bidirectional"))
    )
    (net (code "36") (name "VDD") (class "Default")
      (node (ref "C10") (pin "1") (pinfunction "+_1") (pintype "passive"))
      (node (ref "C11") (pin "1") (pinfunction "1_1") (pintype "passive"))
      (node (ref "C12") (pin "1") (pinfunction "1_1") (pintype "passive"))
      (node (ref "C15") (pin "1") (pinfunction "1_1") (pintype "passive"))
      (node (ref "C16") (pin "2") (pinfunction "2_2") (pintype "bidirectional"))
      (node (ref "C3") (pin "1") (pinfunction "+_1") (pintype "passive"))
      (node (ref "C4") (pin "1") (pinfunction "+_1") (pintype "passive"))
      (node (ref "C6") (pin "1") (pinfunction "1_1") (pintype "passive"))
      (node (ref "C7") (pin "1") (pinfunction "1_1") (pintype "passive"))
      (node (ref "C8") (pin "1") (pinfunction "1_1") (pintype "passive"))
      (node (ref "C9") (pin "1") (pinfunction "1_1") (pintype "passive"))
      (node (ref "D2") (pin "A") (pinfunction "A_A") (pintype "passive"))
      (node (ref "D3") (pin "A") (pinfunction "A_A") (pintype "passive"))
      (node (ref "FB1") (pin "2") (pinfunction "2_2") (pintype "passive"))
      (node (ref "P1") (pin "PAD_PU10") (pinfunction "VDD4_PAD_PU10") (pintype "power_in"))
      (node (ref "P1") (pin "PAD_PU11") (pinfunction "VDD5_PAD_PU11") (pintype "power_in"))
      (node (ref "P1") (pin "PAD_PU12") (pinfunction "VDD6_PAD_PU12") (pintype "power_in"))
      (node (ref "P1") (pin "PAD_PU7") (pinfunction "VDD1_PAD_PU7") (pintype "power_in"))
      (node (ref "P1") (pin "PAD_PU8") (pinfunction "VDD2_PAD_PU8") (pintype "power_in"))
      (node (ref "P1") (pin "PAD_PU9") (pinfunction "VDD3_PAD_PU9") (pintype "power_in"))
      (node (ref "U1") (pin "P$1") (pinfunction "VBAT_P$1") (pintype "power_in"))
      (node (ref "U1") (pin "P$24") (pinfunction "VDD_0_P$24") (pintype "power_in"))
      (node (ref "U1") (pin "P$36") (pinfunction "VDDIO2_P$36") (pintype "power_in"))
      (node (ref "U1") (pin "P$48") (pinfunction "VDD_1_P$48") (pintype "power_in"))
      (node (ref "U2") (pin "1") (pinfunction "VCCIO_1") (pintype "input"))
      (node (ref "U2") (pin "10") (pinfunction "VCC_10") (pintype "power_in"))
      (node (ref "U2") (pin "8") (pinfunction "3V3OUT_8") (pintype "passive"))
      (node (ref "U2") (pin "9") (pinfunction "~{RESET}_9") (pintype "input"))
      (node (ref "U3") (pin "3") (pinfunction "OUT_3") (pintype "output"))
    )
    (net (code "37") (name "VDDA") (class "Default")
      (node (ref "C2") (pin "1") (pinfunction "+_1") (pintype "passive"))
      (node (ref "C5") (pin "1") (pinfunction "1_1") (pintype "passive"))
      (node (ref "FB1") (pin "1") (pinfunction "1_1") (pintype "passive"))
      (node (ref "U1") (pin "P$9") (pinfunction "VDDA_P$9") (pintype "power_in"))
    )
    (net (code "38") (name "VSSA") (class "Default")
      (node (ref "C2") (pin "2") (pinfunction "-_2") (pintype "passive"))
      (node (ref "C5") (pin "2") (pinfunction "2_2") (pintype "passive"))
      (node (ref "R3") (pin "2") (pinfunction "2_2") (pintype "passive"))
      (node (ref "U1") (pin "P$8") (pinfunction "VSS_A_P$8") (pintype "power_in"))
    )
    (net (code "39") (name "unconnected-(PUSB*-Pad4)") (class "Default")
      (node (ref "PUSB*") (pin "4") (pinfunction "4_4") (pintype "passive"))
    )
    (net (code "40") (name "unconnected-(U1-PA7-PadP$17)") (class "Default")
      (node (ref "U1") (pin "P$17") (pinfunction "PA7_P$17") (pintype "bidirectional"))
    )
    (net (code "41") (name "unconnected-(U1-PA8-PadP$29)") (class "Default")
      (node (ref "U1") (pin "P$29") (pinfunction "PA8_P$29") (pintype "bidirectional"))
    )
    (net (code "42") (name "unconnected-(U1-PB0-PadP$18)") (class "Default")
      (node (ref "U1") (pin "P$18") (pinfunction "PB0_P$18") (pintype "bidirectional"))
    )
    (net (code "43") (name "unconnected-(U1-PB2-PadP$20)") (class "Default")
      (node (ref "U1") (pin "P$20") (pinfunction "PB2_P$20") (pintype "bidirectional"))
    )
    (net (code "44") (name "unconnected-(U1-PB5-PadP$41)") (class "Default")
      (node (ref "U1") (pin "P$41") (pinfunction "PB5_P$41") (pintype "bidirectional"))
    )
    (net (code "45") (name "unconnected-(U1-PB6-PadP$42)") (class "Default")
      (node (ref "U1") (pin "P$42") (pinfunction "PB6_P$42") (pintype "bidirectional"))
    )
    (net (code "46") (name "unconnected-(U1-PB7-PadP$43)") (class "Default")
      (node (ref "U1") (pin "P$43") (pinfunction "PB7_P$43") (pintype "bidirectional"))
    )
    (net (code "47") (name "unconnected-(U1-PB8-PadP$45)") (class "Default")
      (node (ref "U1") (pin "P$45") (pinfunction "PB8_P$45") (pintype "bidirectional"))
    )
    (net (code "48") (name "unconnected-(U1-PB9-PadP$46)") (class "Default")
      (node (ref "U1") (pin "P$46") (pinfunction "PB9_P$46") (pintype "bidirectional"))
    )
    (net (code "49") (name "unconnected-(U1-PB12-PadP$25)") (class "Default")
      (node (ref "U1") (pin "P$25") (pinfunction "PB12_P$25") (pintype "bidirectional"))
    )
    (net (code "50") (name "unconnected-(U1-PB13-PadP$26)") (class "Default")
      (node (ref "U1") (pin "P$26") (pinfunction "PB13_P$26") (pintype "bidirectional"))
    )
    (net (code "51") (name "unconnected-(U1-PB15-PadP$28)") (class "Default")
      (node (ref "U1") (pin "P$28") (pinfunction "PB15_P$28") (pintype "bidirectional"))
    )
    (net (code "52") (name "unconnected-(U1-PC13-PadP$2)") (class "Default")
      (node (ref "U1") (pin "P$2") (pinfunction "PC13_P$2") (pintype "bidirectional"))
    )
    (net (code "53") (name "unconnected-(U1-PC15-OSC32_OUT-PadP$4)") (class "Default")
      (node (ref "U1") (pin "P$4") (pinfunction "PC15-OSC32_OUT_P$4") (pintype "bidirectional"))
    )
    (net (code "54") (name "unconnected-(U2-CBUS0-Pad12)") (class "Default")
      (node (ref "U2") (pin "12") (pinfunction "CBUS0_12") (pintype "bidirectional"))
    )
  )
)
